# S7CAS-PLEIADES-CARTE-MERE_P20_Ethernet.net
KiCad netlist of a schematic drawn in Altium Designer
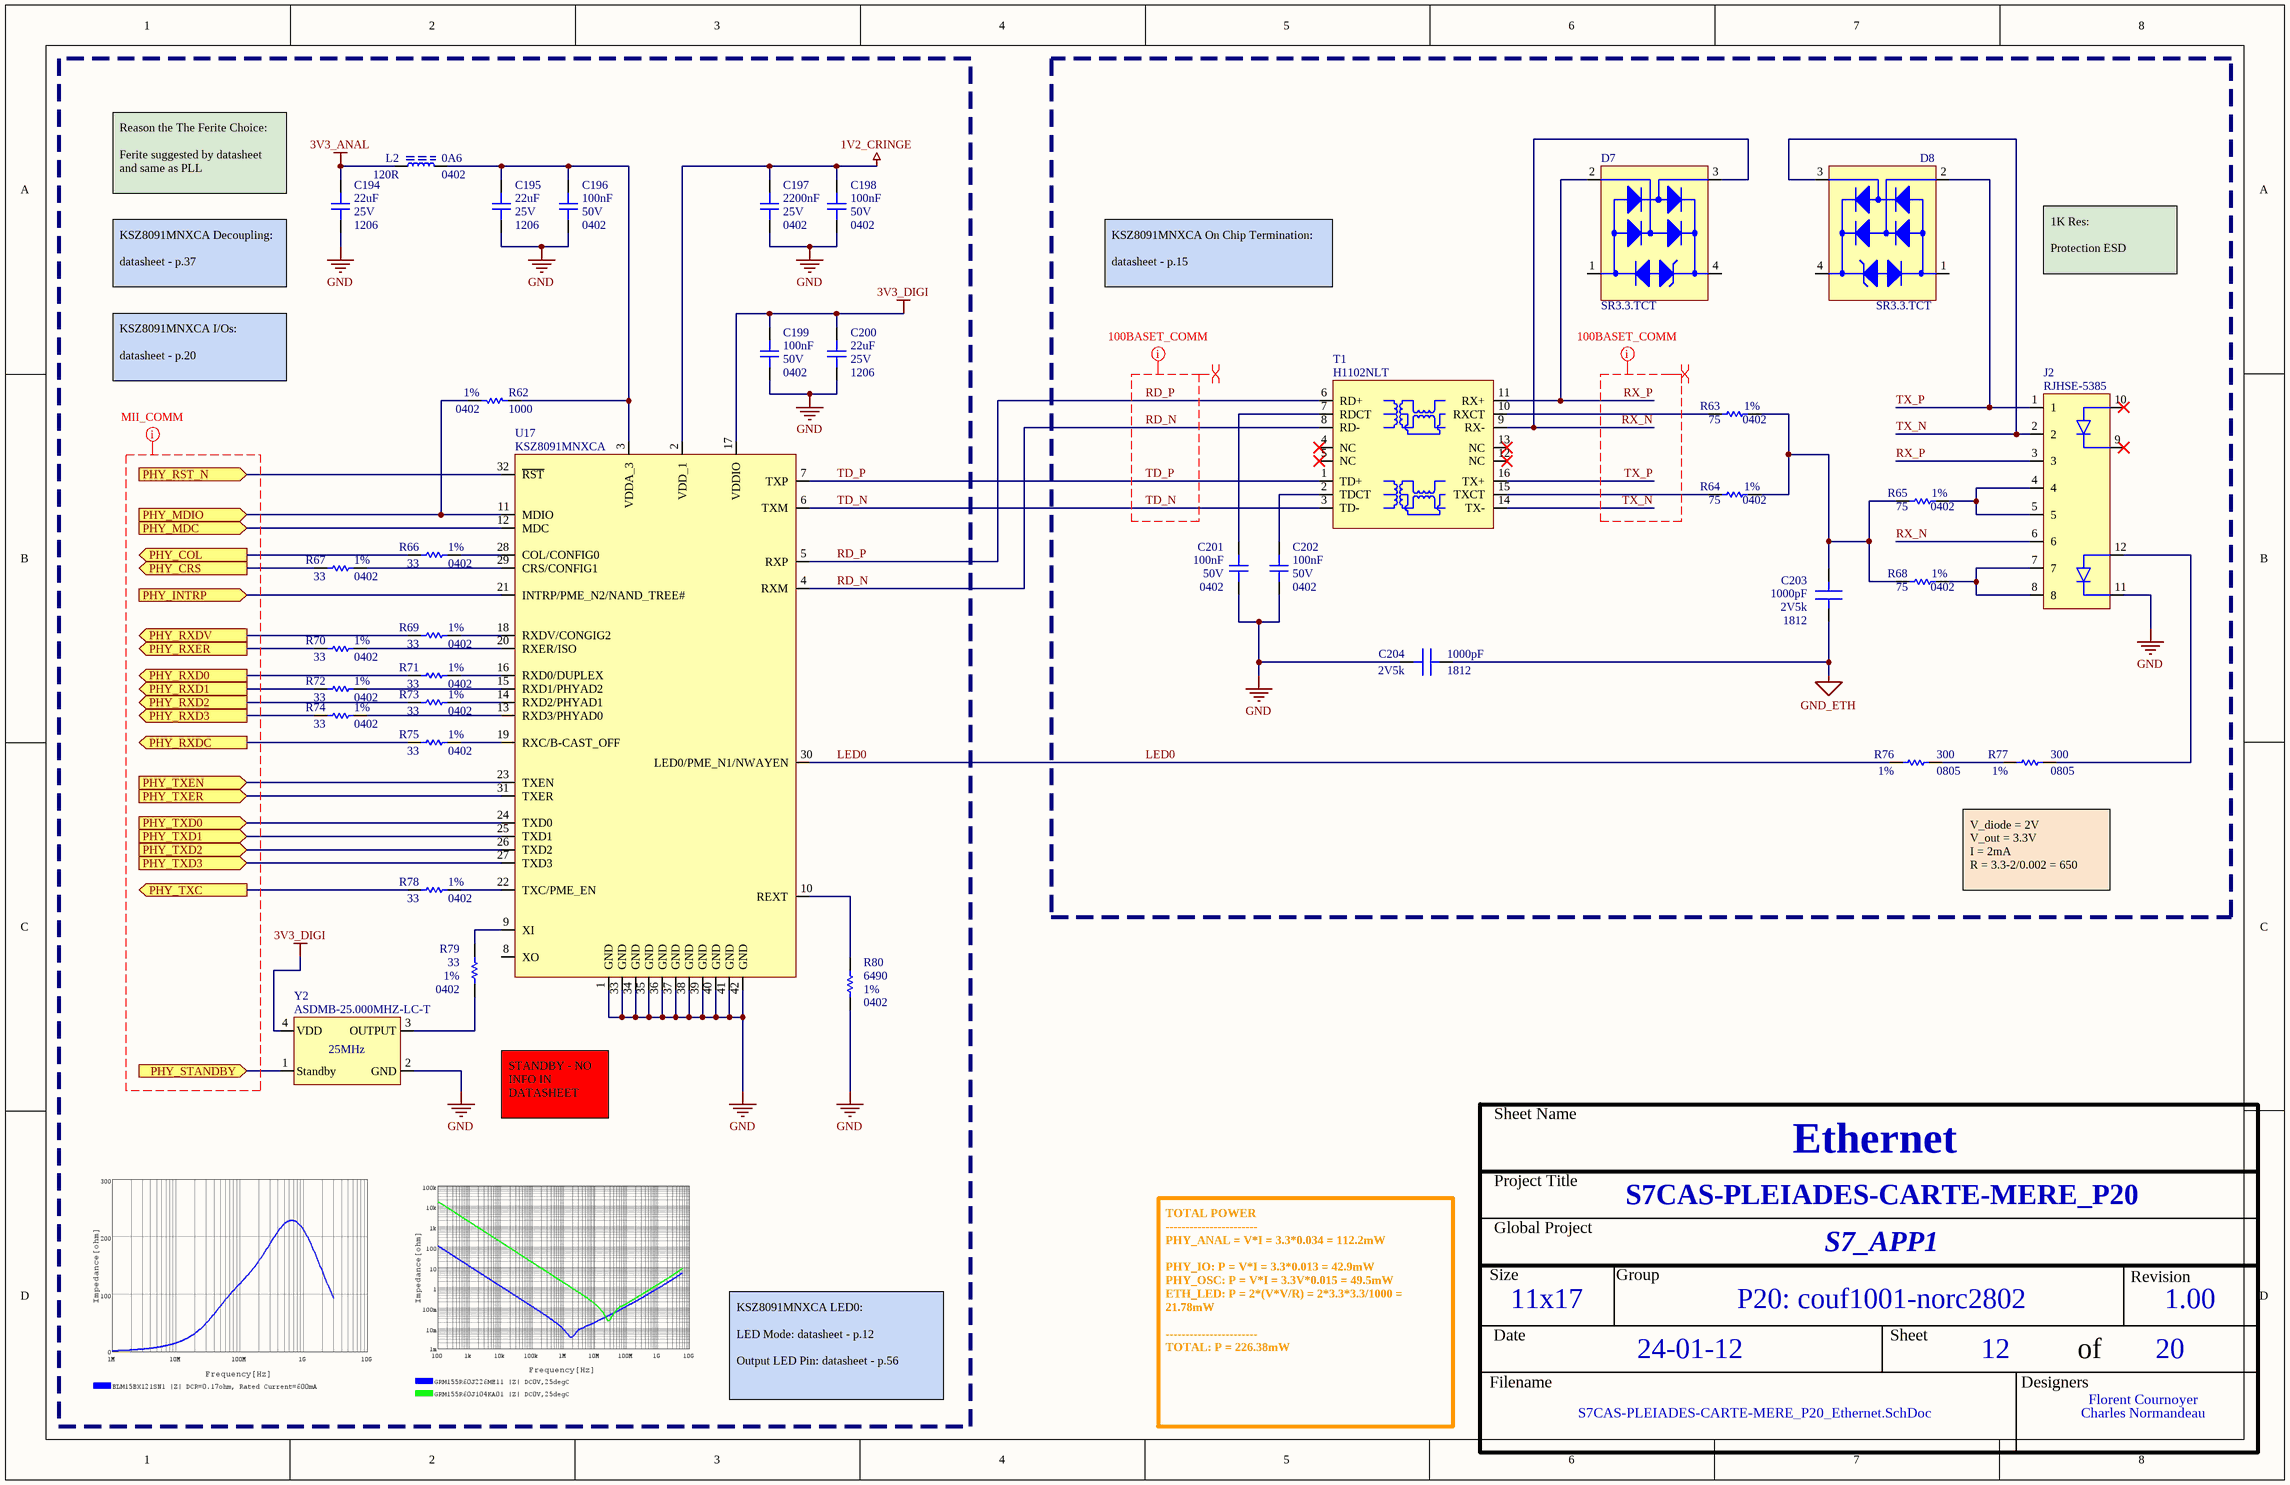
[diagram p0: S7CAS-PLEIADES-CARTE-MERE_P20_Ethernet.SchDoc]

(export (version "E")
  (design (tool "Eeschema 10.0.6"))
  (components
    (comp (ref "C194")
      (value "22uF")
      (footprint "CAP_1206")
      (description "CAP - 1206")
      (fields
        (field (name "MFG PART NUMBER") "GRM31CC81E226KE11")
        (field (name "VOLTAGE") "25V")
        (field (name "PACKAGE") "1206")
        (field (name "CREATEDBY") "Jonathan Bouchard")
      )
      (libsource (lib "S7CAS_LIB2023") (part "CAP - 1206"))
    )
    (comp (ref "C195")
      (value "22uF")
      (footprint "CAP_1206")
      (description "CAP - 1206")
      (fields
        (field (name "MFG PART NUMBER") "GRM31CC81E226KE11")
        (field (name "VOLTAGE") "25V")
        (field (name "PACKAGE") "1206")
        (field (name "CREATEDBY") "Jonathan Bouchard")
      )
      (libsource (lib "S7CAS_LIB2023") (part "CAP - 1206"))
    )
    (comp (ref "C196")
      (value "100nF")
      (footprint "CAP_0402")
      (description "CAP - 0402")
      (fields
        (field (name "MFG PART NUMBER") "GRM155R61H104KE14")
        (field (name "VOLTAGE") "50V")
        (field (name "PACKAGE") "0402")
        (field (name "CREATEDBY") "Jonathan Bouchard")
      )
      (libsource (lib "S7CAS_LIB2023") (part "CAP - 0402"))
    )
    (comp (ref "C197")
      (value "2200nF")
      (footprint "CAP_0402")
      (description "CAP - 0402")
      (fields
        (field (name "MFG PART NUMBER") "GRM155R61E225KE11")
        (field (name "VOLTAGE") "25V")
        (field (name "PACKAGE") "0402")
        (field (name "CREATEDBY") "Jonathan Bouchard")
      )
      (libsource (lib "S7CAS_LIB2023") (part "CAP - 0402"))
    )
    (comp (ref "C198")
      (value "100nF")
      (footprint "CAP_0402")
      (description "CAP - 0402")
      (fields
        (field (name "MFG PART NUMBER") "GRM155R61H104KE14")
        (field (name "VOLTAGE") "50V")
        (field (name "PACKAGE") "0402")
        (field (name "CREATEDBY") "Jonathan Bouchard")
      )
      (libsource (lib "S7CAS_LIB2023") (part "CAP - 0402"))
    )
    (comp (ref "C199")
      (value "100nF")
      (footprint "CAP_0402")
      (description "CAP - 0402")
      (fields
        (field (name "MFG PART NUMBER") "GRM155R61H104KE14")
        (field (name "VOLTAGE") "50V")
        (field (name "PACKAGE") "0402")
        (field (name "CREATEDBY") "Jonathan Bouchard")
      )
      (libsource (lib "S7CAS_LIB2023") (part "CAP - 0402"))
    )
    (comp (ref "C200")
      (value "22uF")
      (footprint "CAP_1206")
      (description "CAP - 1206")
      (fields
        (field (name "MFG PART NUMBER") "GRM31CC81E226KE11")
        (field (name "VOLTAGE") "25V")
        (field (name "PACKAGE") "1206")
        (field (name "CREATEDBY") "Jonathan Bouchard")
      )
      (libsource (lib "S7CAS_LIB2023") (part "CAP - 1206"))
    )
    (comp (ref "C201")
      (value "100nF")
      (footprint "CAP_0402")
      (description "CAP - 0402")
      (fields
        (field (name "MFG PART NUMBER") "GRM155R61H104KE14")
        (field (name "VOLTAGE") "50V")
        (field (name "PACKAGE") "0402")
        (field (name "CREATEDBY") "Jonathan Bouchard")
      )
      (libsource (lib "S7CAS_LIB2023") (part "CAP - 0402"))
    )
    (comp (ref "C202")
      (value "100nF")
      (footprint "CAP_0402")
      (description "CAP - 0402")
      (fields
        (field (name "MFG PART NUMBER") "GRM155R61H104KE14")
        (field (name "VOLTAGE") "50V")
        (field (name "PACKAGE") "0402")
        (field (name "CREATEDBY") "Jonathan Bouchard")
      )
      (libsource (lib "S7CAS_LIB2023") (part "CAP - 0402"))
    )
    (comp (ref "C203")
      (value "1000pF")
      (footprint "CAP_CER_1812")
      (description "CAP - CER 1000PF 2.5KV X7R - 1812")
      (fields
        (field (name "TOLERANCE") "10%")
        (field (name "PACKAGE") "1812")
        (field (name "VOLTAGE RATING") "2V5k")
        (field (name "Comment") "1812WC102KAT1A")
      )
      (libsource (lib "LIB_TEMP_P20_FLORENT_COURNOYER_SCH") (part "CAP_CER_1812WC102KAT1A"))
    )
    (comp (ref "C204")
      (value "1000pF")
      (footprint "CAP_CER_1812")
      (description "CAP - CER 1000PF 2.5KV X7R - 1812")
      (fields
        (field (name "TOLERANCE") "10%")
        (field (name "PACKAGE") "1812")
        (field (name "VOLTAGE RATING") "2V5k")
        (field (name "Comment") "1812WC102KAT1A")
      )
      (libsource (lib "LIB_TEMP_P20_FLORENT_COURNOYER_SCH") (part "CAP_CER_1812WC102KAT1A"))
    )
    (comp (ref "D7")
      (value "SR3.3.TCT")
      (footprint "TVS_SR3.3.TCT")
      (description "TVS - DIODE ARRAY 3.3V 150W - SOT143-4")
      (fields
        (field (name "MFG") "Semtech")
        (field (name "POWER") "150W")
        (field (name "CREATEDBY") "Jonathan Bouchard")
      )
      (libsource (lib "S7CAS_LIB2023") (part "TVS_SR3.3.TCT"))
    )
    (comp (ref "D8")
      (value "SR3.3.TCT")
      (footprint "TVS_SR3.3.TCT")
      (description "TVS - DIODE ARRAY 3.3V 150W - SOT143-4")
      (fields
        (field (name "MFG") "Semtech")
        (field (name "POWER") "150W")
        (field (name "CREATEDBY") "Jonathan Bouchard")
      )
      (libsource (lib "") (part "TVS_SR3.3.TCT_1"))
    )
    (comp (ref "J2")
      (value "RJHSE-5385")
      (footprint "CONN_ETHERNET_RJHSE-5385")
      (description "CONN - MOD JACK RJ45 R/A ETHERNET - TH")
      (fields (field (name "MFG") "Amphenol") (field (name "CREATEDBY") "Jonathan Bouchard"))
      (libsource (lib "S7CAS_LIB2023") (part "CONN_ETHERNET_RJHSE-5385"))
    )
    (comp (ref "L2")
      (value "120R")
      (footprint "FER_0402")
      (description "FER - 0402")
      (fields
        (field (name "MFG PART NUMBER") "BLM15BX121SN1")
        (field (name "CURRENT") "0A6")
        (field (name "PACKAGE") "0402")
        (field (name "CREATEDBY") "Jonathan Bouchard")
      )
      (libsource (lib "S7CAS_LIB2023") (part "FER - 0402"))
    )
    (comp (ref "R62")
      (value "1000")
      (footprint "RES_0402")
      (description "RES - 0402")
      (fields
        (field (name "VOLTAGE") "50V")
        (field (name "MFG PART NUMBER") "MCS04020C1001FE000")
        (field (name "PACKAGE") "0402")
        (field (name "PRECISION") "1%")
        (field (name "CREATEDBY") "Jonathan Bouchard")
      )
      (libsource (lib "S7CAS_LIB2023") (part "RES - 0402"))
    )
    (comp (ref "R63")
      (value "75")
      (footprint "RES_0402")
      (description "RES - 0402")
      (fields
        (field (name "VOLTAGE") "50V")
        (field (name "MFG PART NUMBER") "SG73P")
        (field (name "PACKAGE") "0402")
        (field (name "PRECISION") "1%")
        (field (name "CREATEDBY") "Jonathan Bouchard")
      )
      (libsource (lib "S7CAS_LIB2023") (part "RES - 0402"))
    )
    (comp (ref "R64")
      (value "75")
      (footprint "RES_0402")
      (description "RES - 0402")
      (fields
        (field (name "VOLTAGE") "50V")
        (field (name "MFG PART NUMBER") "SG73P")
        (field (name "PACKAGE") "0402")
        (field (name "PRECISION") "1%")
        (field (name "CREATEDBY") "Jonathan Bouchard")
      )
      (libsource (lib "S7CAS_LIB2023") (part "RES - 0402"))
    )
    (comp (ref "R65")
      (value "75")
      (footprint "RES_0402")
      (description "RES - 0402")
      (fields
        (field (name "VOLTAGE") "50V")
        (field (name "MFG PART NUMBER") "SG73P")
        (field (name "PACKAGE") "0402")
        (field (name "PRECISION") "1%")
        (field (name "CREATEDBY") "Jonathan Bouchard")
      )
      (libsource (lib "S7CAS_LIB2023") (part "RES - 0402"))
    )
    (comp (ref "R66")
      (value "33")
      (footprint "RES_0402")
      (description "RES - 0402")
      (fields
        (field (name "VOLTAGE") "50V")
        (field (name "MFG PART NUMBER") "CRCW040233R0FKEDC")
        (field (name "PACKAGE") "0402")
        (field (name "PRECISION") "1%")
        (field (name "CREATEDBY") "Jonathan Bouchard")
      )
      (libsource (lib "S7CAS_LIB2023") (part "RES - 0402"))
    )
    (comp (ref "R67")
      (value "33")
      (footprint "RES_0402")
      (description "RES - 0402")
      (fields
        (field (name "VOLTAGE") "50V")
        (field (name "MFG PART NUMBER") "CRCW040233R0FKEDC")
        (field (name "PACKAGE") "0402")
        (field (name "PRECISION") "1%")
        (field (name "CREATEDBY") "Jonathan Bouchard")
      )
      (libsource (lib "S7CAS_LIB2023") (part "RES - 0402"))
    )
    (comp (ref "R68")
      (value "75")
      (footprint "RES_0402")
      (description "RES - 0402")
      (fields
        (field (name "VOLTAGE") "50V")
        (field (name "MFG PART NUMBER") "SG73P")
        (field (name "PACKAGE") "0402")
        (field (name "PRECISION") "1%")
        (field (name "CREATEDBY") "Jonathan Bouchard")
      )
      (libsource (lib "S7CAS_LIB2023") (part "RES - 0402"))
    )
    (comp (ref "R69")
      (value "33")
      (footprint "RES_0402")
      (description "RES - 0402")
      (fields
        (field (name "VOLTAGE") "50V")
        (field (name "MFG PART NUMBER") "CRCW040233R0FKEDC")
        (field (name "PACKAGE") "0402")
        (field (name "PRECISION") "1%")
        (field (name "CREATEDBY") "Jonathan Bouchard")
      )
      (libsource (lib "S7CAS_LIB2023") (part "RES - 0402"))
    )
    (comp (ref "R70")
      (value "33")
      (footprint "RES_0402")
      (description "RES - 0402")
      (fields
        (field (name "VOLTAGE") "50V")
        (field (name "MFG PART NUMBER") "CRCW040233R0FKEDC")
        (field (name "PACKAGE") "0402")
        (field (name "PRECISION") "1%")
        (field (name "CREATEDBY") "Jonathan Bouchard")
      )
      (libsource (lib "S7CAS_LIB2023") (part "RES - 0402"))
    )
    (comp (ref "R71")
      (value "33")
      (footprint "RES_0402")
      (description "RES - 0402")
      (fields
        (field (name "VOLTAGE") "50V")
        (field (name "MFG PART NUMBER") "CRCW040233R0FKEDC")
        (field (name "PACKAGE") "0402")
        (field (name "PRECISION") "1%")
        (field (name "CREATEDBY") "Jonathan Bouchard")
      )
      (libsource (lib "S7CAS_LIB2023") (part "RES - 0402"))
    )
    (comp (ref "R72")
      (value "33")
      (footprint "RES_0402")
      (description "RES - 0402")
      (fields
        (field (name "VOLTAGE") "50V")
        (field (name "MFG PART NUMBER") "CRCW040233R0FKEDC")
        (field (name "PACKAGE") "0402")
        (field (name "PRECISION") "1%")
        (field (name "CREATEDBY") "Jonathan Bouchard")
      )
      (libsource (lib "S7CAS_LIB2023") (part "RES - 0402"))
    )
    (comp (ref "R73")
      (value "33")
      (footprint "RES_0402")
      (description "RES - 0402")
      (fields
        (field (name "VOLTAGE") "50V")
        (field (name "MFG PART NUMBER") "CRCW040233R0FKEDC")
        (field (name "PACKAGE") "0402")
        (field (name "PRECISION") "1%")
        (field (name "CREATEDBY") "Jonathan Bouchard")
      )
      (libsource (lib "S7CAS_LIB2023") (part "RES - 0402"))
    )
    (comp (ref "R74")
      (value "33")
      (footprint "RES_0402")
      (description "RES - 0402")
      (fields
        (field (name "VOLTAGE") "50V")
        (field (name "MFG PART NUMBER") "CRCW040233R0FKEDC")
        (field (name "PACKAGE") "0402")
        (field (name "PRECISION") "1%")
        (field (name "CREATEDBY") "Jonathan Bouchard")
      )
      (libsource (lib "S7CAS_LIB2023") (part "RES - 0402"))
    )
    (comp (ref "R75")
      (value "33")
      (footprint "RES_0402")
      (description "RES - 0402")
      (fields
        (field (name "VOLTAGE") "50V")
        (field (name "MFG PART NUMBER") "CRCW040233R0FKEDC")
        (field (name "PACKAGE") "0402")
        (field (name "PRECISION") "1%")
        (field (name "CREATEDBY") "Jonathan Bouchard")
      )
      (libsource (lib "S7CAS_LIB2023") (part "RES - 0402"))
    )
    (comp (ref "R76")
      (value "300")
      (footprint "RES_0805")
      (description "RES - 0805")
      (fields
        (field (name "MFG PART NUMBER") "CRM0805-FX-1000ELF")
        (field (name "PACKAGE") "0805")
        (field (name "PRECISION") "1%")
        (field (name "CREATEDBY") "Jonathan Bouchard")
      )
      (libsource (lib "S7CAS_LIB2023") (part "RES - 0805"))
    )
    (comp (ref "R77")
      (value "300")
      (footprint "RES_0805")
      (description "RES - 0805")
      (fields
        (field (name "MFG PART NUMBER") "CRM0805-FX-1000ELF")
        (field (name "PACKAGE") "0805")
        (field (name "PRECISION") "1%")
        (field (name "CREATEDBY") "Jonathan Bouchard")
      )
      (libsource (lib "S7CAS_LIB2023") (part "RES - 0805"))
    )
    (comp (ref "R78")
      (value "33")
      (footprint "RES_0402")
      (description "RES - 0402")
      (fields
        (field (name "VOLTAGE") "50V")
        (field (name "MFG PART NUMBER") "CRCW040233R0FKEDC")
        (field (name "PACKAGE") "0402")
        (field (name "PRECISION") "1%")
        (field (name "CREATEDBY") "Jonathan Bouchard")
      )
      (libsource (lib "S7CAS_LIB2023") (part "RES - 0402"))
    )
    (comp (ref "R79")
      (value "33")
      (footprint "RES_0402")
      (description "RES - 0402")
      (fields
        (field (name "VOLTAGE") "50V")
        (field (name "MFG PART NUMBER") "CRCW040233R0FKEDC")
        (field (name "PACKAGE") "0402")
        (field (name "PRECISION") "1%")
        (field (name "CREATEDBY") "Jonathan Bouchard")
      )
      (libsource (lib "S7CAS_LIB2023") (part "RES - 0402"))
    )
    (comp (ref "R80")
      (value "6490")
      (footprint "RES_0402")
      (description "RES - 0402")
      (fields
        (field (name "VOLTAGE") "50V")
        (field (name "MFG PART NUMBER") "CRCW04026K49FKEDC")
        (field (name "PACKAGE") "0402")
        (field (name "PRECISION") "1%")
        (field (name "CREATEDBY") "Jonathan Bouchard")
      )
      (libsource (lib "S7CAS_LIB2023") (part "RES - 0402"))
    )
    (comp (ref "T1")
      (value "H1102NLT")
      (footprint "TRANSFO_H1102NLT")
      (description "TRANSFO - ETHERNET 10/100B-TX - SMD-16")
      (fields (field (name "MFG") "Pulse Eng.") (field (name "CREATEDBY") "Jonathan Bouchard"))
      (libsource (lib "S7CAS_LIB2023") (part "TRANSFO_H1102NLT"))
    )
    (comp (ref "U17")
      (value "KSZ8091MNXCA")
      (footprint "COM_ETH_PHY_KSZ8091MNXCA")
      (description "COM - ETHERNET PHY 10/100 - QFN-32")
      (fields
        (field (name "VOLTAGE") "1.8V, 2.5V, 3.3V")
        (field (name "MFG") "Micrel")
        (field (name "CREATEDBY") "Jonathan Bouchard")
      )
      (libsource (lib "S7CAS_LIB2023") (part "COM_ETH_PHY_KSZ8091MNXCA"))
    )
    (comp (ref "Y2")
      (value "ASDMB-25.000MHZ-LC-T")
      (footprint "OSC_ASDMB-25.000MHZ-LC-T")
      (description "OSC - 25MHz XO (Standard) LVCMOS - 4-SMD, No Lead")
      (fields
        (field (name "TOLERANCE") "±50ppm")
        (field (name "CREATEDBY/DATE") "Joël Lemay 2019-03-29")
        (field (name "VERIFIEDBY") "C. Paulin - 29 mai 2019")
      )
      (libsource (lib "S7CAS_LIB2023") (part "OSC_ASDMB-25.000MHZ-LC-T"))
    )
  )
  (nets
    (net (code "1") (name "/LED0") (class "Default")
      (node (ref "R76") (pin "2") (pinfunction "2_2") (pintype "passive"))
      (node (ref "U17") (pin "30") (pinfunction "LED0/PME_N1/NWAYEN_30") (pintype "passive"))
    )
    (net (code "2") (name "/PHY_COL") (class "Default")
      (node (ref "R66") (pin "2") (pinfunction "2_2") (pintype "passive"))
    )
    (net (code "3") (name "/PHY_CRS") (class "Default")
      (node (ref "R67") (pin "2") (pinfunction "2_2") (pintype "passive"))
    )
    (net (code "4") (name "/PHY_INTRP") (class "Default")
      (node (ref "U17") (pin "21") (pinfunction "INTRP/PME_N2/NAND_TREE#_21") (pintype "passive"))
    )
    (net (code "5") (name "/PHY_MDC") (class "Default")
      (node (ref "U17") (pin "12") (pinfunction "MDC_12") (pintype "passive"))
    )
    (net (code "6") (name "/PHY_MDIO") (class "Default")
      (node (ref "R62") (pin "1") (pinfunction "1_1") (pintype "passive"))
      (node (ref "U17") (pin "11") (pinfunction "MDIO_11") (pintype "passive"))
    )
    (net (code "7") (name "/PHY_RST_N") (class "Default")
      (node (ref "U17") (pin "32") (pinfunction "RST_32") (pintype "passive"))
    )
    (net (code "8") (name "/PHY_RXD0") (class "Default")
      (node (ref "R71") (pin "2") (pinfunction "2_2") (pintype "passive"))
    )
    (net (code "9") (name "/PHY_RXD1") (class "Default")
      (node (ref "R72") (pin "2") (pinfunction "2_2") (pintype "passive"))
    )
    (net (code "10") (name "/PHY_RXD2") (class "Default")
      (node (ref "R73") (pin "2") (pinfunction "2_2") (pintype "passive"))
    )
    (net (code "11") (name "/PHY_RXD3") (class "Default")
      (node (ref "R74") (pin "2") (pinfunction "2_2") (pintype "passive"))
    )
    (net (code "12") (name "/PHY_RXDC") (class "Default")
      (node (ref "R75") (pin "2") (pinfunction "2_2") (pintype "passive"))
    )
    (net (code "13") (name "/PHY_RXDV") (class "Default")
      (node (ref "R69") (pin "2") (pinfunction "2_2") (pintype "passive"))
    )
    (net (code "14") (name "/PHY_RXER") (class "Default")
      (node (ref "R70") (pin "2") (pinfunction "2_2") (pintype "passive"))
    )
    (net (code "15") (name "/PHY_STANDBY") (class "Default")
      (node (ref "Y2") (pin "1") (pinfunction "Standby_1") (pintype "passive"))
    )
    (net (code "16") (name "/PHY_TXC") (class "Default")
      (node (ref "R78") (pin "2") (pinfunction "2_2") (pintype "passive"))
    )
    (net (code "17") (name "/PHY_TXD0") (class "Default")
      (node (ref "U17") (pin "24") (pinfunction "TXD0_24") (pintype "passive"))
    )
    (net (code "18") (name "/PHY_TXD1") (class "Default")
      (node (ref "U17") (pin "25") (pinfunction "TXD1_25") (pintype "passive"))
    )
    (net (code "19") (name "/PHY_TXD2") (class "Default")
      (node (ref "U17") (pin "26") (pinfunction "TXD2_26") (pintype "passive"))
    )
    (net (code "20") (name "/PHY_TXD3") (class "Default")
      (node (ref "U17") (pin "27") (pinfunction "TXD3_27") (pintype "passive"))
    )
    (net (code "21") (name "/PHY_TXEN") (class "Default")
      (node (ref "U17") (pin "23") (pinfunction "TXEN_23") (pintype "passive"))
    )
    (net (code "22") (name "/PHY_TXER") (class "Default")
      (node (ref "U17") (pin "31") (pinfunction "TXER_31") (pintype "passive"))
    )
    (net (code "23") (name "/RD_N") (class "Default")
      (node (ref "T1") (pin "8") (pinfunction "RD-_8") (pintype "passive"))
      (node (ref "U17") (pin "4") (pinfunction "RXM_4") (pintype "passive"))
    )
    (net (code "24") (name "/RD_P") (class "Default")
      (node (ref "T1") (pin "6") (pinfunction "RD+_6") (pintype "passive"))
      (node (ref "U17") (pin "5") (pinfunction "RXP_5") (pintype "passive"))
    )
    (net (code "25") (name "/RX_N") (class "Default")
      (node (ref "D7") (pin "3") (pintype "passive"))
      (node (ref "J2") (pin "6") (pinfunction "6_6") (pintype "passive"))
      (node (ref "T1") (pin "9") (pinfunction "RX-_9") (pintype "passive"))
    )
    (net (code "26") (name "/RX_P") (class "Default")
      (node (ref "D7") (pin "2") (pinfunction "VN_2") (pintype "passive"))
      (node (ref "J2") (pin "3") (pinfunction "3_3") (pintype "passive"))
      (node (ref "T1") (pin "11") (pinfunction "RX+_11") (pintype "passive"))
    )
    (net (code "27") (name "/TD_N") (class "Default")
      (node (ref "T1") (pin "3") (pinfunction "TD-_3") (pintype "passive"))
      (node (ref "U17") (pin "6") (pinfunction "TXM_6") (pintype "passive"))
    )
    (net (code "28") (name "/TD_P") (class "Default")
      (node (ref "T1") (pin "1") (pinfunction "TD+_1") (pintype "passive"))
      (node (ref "U17") (pin "7") (pinfunction "TXP_7") (pintype "passive"))
    )
    (net (code "29") (name "/TX_N") (class "Default")
      (node (ref "D8") (pin "3") (pintype "passive"))
      (node (ref "J2") (pin "2") (pinfunction "2_2") (pintype "passive"))
      (node (ref "T1") (pin "14") (pinfunction "TX-_14") (pintype "passive"))
    )
    (net (code "30") (name "/TX_P") (class "Default")
      (node (ref "D8") (pin "2") (pinfunction "VN_2") (pintype "passive"))
      (node (ref "J2") (pin "1") (pinfunction "1_1") (pintype "passive"))
      (node (ref "T1") (pin "16") (pinfunction "TX+_16") (pintype "passive"))
    )
    (net (code "31") (name "1V2_CRINGE") (class "Default")
      (node (ref "C197") (pin "2") (pinfunction "2_2") (pintype "passive"))
      (node (ref "C198") (pin "2") (pinfunction "2_2") (pintype "passive"))
      (node (ref "U17") (pin "2") (pinfunction "VDD_1_2") (pintype "power_in"))
    )
    (net (code "32") (name "3V3_ANAL") (class "Default")
      (node (ref "C194") (pin "2") (pinfunction "2_2") (pintype "passive"))
      (node (ref "L2") (pin "2") (pinfunction "2_2") (pintype "passive"))
    )
    (net (code "33") (name "3V3_DIGI") (class "Default")
      (node (ref "C199") (pin "2") (pinfunction "2_2") (pintype "passive"))
      (node (ref "C200") (pin "2") (pinfunction "2_2") (pintype "passive"))
      (node (ref "U17") (pin "17") (pinfunction "VDDIO_17") (pintype "power_in"))
      (node (ref "Y2") (pin "4") (pinfunction "VDD_4") (pintype "passive"))
    )
    (net (code "34") (name "GND") (class "Default")
      (node (ref "C194") (pin "1") (pinfunction "1_1") (pintype "passive"))
      (node (ref "C195") (pin "1") (pinfunction "1_1") (pintype "passive"))
      (node (ref "C196") (pin "1") (pinfunction "1_1") (pintype "passive"))
      (node (ref "C197") (pin "1") (pinfunction "1_1") (pintype "passive"))
      (node (ref "C198") (pin "1") (pinfunction "1_1") (pintype "passive"))
      (node (ref "C199") (pin "1") (pinfunction "1_1") (pintype "passive"))
      (node (ref "C200") (pin "1") (pinfunction "1_1") (pintype "passive"))
      (node (ref "C201") (pin "1") (pinfunction "1_1") (pintype "passive"))
      (node (ref "C202") (pin "1") (pinfunction "1_1") (pintype "passive"))
      (node (ref "C204") (pin "2") (pinfunction "2_2") (pintype "passive"))
      (node (ref "J2") (pin "11") (pinfunction "LED2_K_11") (pintype "passive"))
      (node (ref "R80") (pin "1") (pinfunction "1_1") (pintype "passive"))
      (node (ref "U17") (pin "1") (pinfunction "GND_1") (pintype "passive"))
      (node (ref "U17") (pin "33") (pinfunction "GND_33") (pintype "passive"))
      (node (ref "U17") (pin "34") (pinfunction "GND_34") (pintype "passive"))
      (node (ref "U17") (pin "35") (pinfunction "GND_35") (pintype "passive"))
      (node (ref "U17") (pin "36") (pinfunction "GND_36") (pintype "passive"))
      (node (ref "U17") (pin "37") (pinfunction "GND_37") (pintype "passive"))
      (node (ref "U17") (pin "38") (pinfunction "GND_38") (pintype "passive"))
      (node (ref "U17") (pin "39") (pinfunction "GND_39") (pintype "passive"))
      (node (ref "U17") (pin "40") (pinfunction "GND_40") (pintype "passive"))
      (node (ref "U17") (pin "41") (pinfunction "GND_41") (pintype "passive"))
      (node (ref "U17") (pin "42") (pinfunction "GND_42") (pintype "passive"))
      (node (ref "Y2") (pin "2") (pinfunction "GND_2") (pintype "passive"))
    )
    (net (code "35") (name "GND_ETH") (class "Default")
      (node (ref "C203") (pin "2") (pinfunction "2_2") (pintype "passive"))
      (node (ref "C204") (pin "1") (pinfunction "1_1") (pintype "passive"))
    )
    (net (code "36") (name "Net-(C203-Pad1)") (class "Default")
      (node (ref "C203") (pin "1") (pinfunction "1_1") (pintype "passive"))
      (node (ref "R63") (pin "1") (pinfunction "1_1") (pintype "passive"))
      (node (ref "R64") (pin "1") (pinfunction "1_1") (pintype "passive"))
      (node (ref "R65") (pin "2") (pinfunction "2_2") (pintype "passive"))
      (node (ref "R68") (pin "2") (pinfunction "2_2") (pintype "passive"))
    )
    (net (code "37") (name "Net-(J2-LED2_A)") (class "Default")
      (node (ref "J2") (pin "12") (pinfunction "LED2_A_12") (pintype "passive"))
      (node (ref "R77") (pin "1") (pinfunction "1_1") (pintype "passive"))
    )
    (net (code "38") (name "Net-(J2-Pad4)") (class "Default")
      (node (ref "J2") (pin "4") (pinfunction "4_4") (pintype "passive"))
      (node (ref "J2") (pin "5") (pinfunction "5_5") (pintype "passive"))
      (node (ref "R65") (pin "1") (pinfunction "1_1") (pintype "passive"))
    )
    (net (code "39") (name "Net-(J2-Pad7)") (class "Default")
      (node (ref "J2") (pin "7") (pinfunction "7_7") (pintype "passive"))
      (node (ref "J2") (pin "8") (pinfunction "8_8") (pintype "passive"))
      (node (ref "R68") (pin "1") (pinfunction "1_1") (pintype "passive"))
    )
    (net (code "40") (name "Net-(R76-Pad1)") (class "Default")
      (node (ref "R76") (pin "1") (pinfunction "1_1") (pintype "passive"))
      (node (ref "R77") (pin "2") (pinfunction "2_2") (pintype "passive"))
    )
    (net (code "41") (name "Net-(T1-RDCT)") (class "Default")
      (node (ref "C201") (pin "2") (pinfunction "2_2") (pintype "passive"))
      (node (ref "T1") (pin "7") (pinfunction "RDCT_7") (pintype "passive"))
    )
    (net (code "42") (name "Net-(T1-RXCT)") (class "Default")
      (node (ref "R63") (pin "2") (pinfunction "2_2") (pintype "passive"))
      (node (ref "T1") (pin "10") (pinfunction "RXCT_10") (pintype "passive"))
    )
    (net (code "43") (name "Net-(T1-TDCT)") (class "Default")
      (node (ref "C202") (pin "2") (pinfunction "2_2") (pintype "passive"))
      (node (ref "T1") (pin "2") (pinfunction "TDCT_2") (pintype "passive"))
    )
    (net (code "44") (name "Net-(T1-TXCT)") (class "Default")
      (node (ref "R64") (pin "2") (pinfunction "2_2") (pintype "passive"))
      (node (ref "T1") (pin "15") (pinfunction "TXCT_15") (pintype "passive"))
    )
    (net (code "45") (name "Net-(U17-COL{slash}CONFIG0)") (class "Default")
      (node (ref "R66") (pin "1") (pinfunction "1_1") (pintype "passive"))
      (node (ref "U17") (pin "28") (pinfunction "COL/CONFIG0_28") (pintype "passive"))
    )
    (net (code "46") (name "Net-(U17-CRS{slash}CONFIG1)") (class "Default")
      (node (ref "R67") (pin "1") (pinfunction "1_1") (pintype "passive"))
      (node (ref "U17") (pin "29") (pinfunction "CRS/CONFIG1_29") (pintype "passive"))
    )
    (net (code "47") (name "Net-(U17-REXT)") (class "Default")
      (node (ref "R80") (pin "2") (pinfunction "2_2") (pintype "passive"))
      (node (ref "U17") (pin "10") (pinfunction "REXT_10") (pintype "passive"))
    )
    (net (code "48") (name "Net-(U17-RXC{slash}B-CAST_OFF)") (class "Default")
      (node (ref "R75") (pin "1") (pinfunction "1_1") (pintype "passive"))
      (node (ref "U17") (pin "19") (pinfunction "RXC/B-CAST_OFF_19") (pintype "passive"))
    )
    (net (code "49") (name "Net-(U17-RXD0{slash}DUPLEX)") (class "Default")
      (node (ref "R71") (pin "1") (pinfunction "1_1") (pintype "passive"))
      (node (ref "U17") (pin "16") (pinfunction "RXD0/DUPLEX_16") (pintype "passive"))
    )
    (net (code "50") (name "Net-(U17-RXD1{slash}PHYAD2)") (class "Default")
      (node (ref "R72") (pin "1") (pinfunction "1_1") (pintype "passive"))
      (node (ref "U17") (pin "15") (pinfunction "RXD1/PHYAD2_15") (pintype "passive"))
    )
    (net (code "51") (name "Net-(U17-RXD2{slash}PHYAD1)") (class "Default")
      (node (ref "R73") (pin "1") (pinfunction "1_1") (pintype "passive"))
      (node (ref "U17") (pin "14") (pinfunction "RXD2/PHYAD1_14") (pintype "passive"))
    )
    (net (code "52") (name "Net-(U17-RXD3{slash}PHYAD0)") (class "Default")
      (node (ref "R74") (pin "1") (pinfunction "1_1") (pintype "passive"))
      (node (ref "U17") (pin "13") (pinfunction "RXD3/PHYAD0_13") (pintype "passive"))
    )
    (net (code "53") (name "Net-(U17-RXDV{slash}CONGIG2)") (class "Default")
      (node (ref "R69") (pin "1") (pinfunction "1_1") (pintype "passive"))
      (node (ref "U17") (pin "18") (pinfunction "RXDV/CONGIG2_18") (pintype "passive"))
    )
    (net (code "54") (name "Net-(U17-RXER{slash}ISO)") (class "Default")
      (node (ref "R70") (pin "1") (pinfunction "1_1") (pintype "passive"))
      (node (ref "U17") (pin "20") (pinfunction "RXER/ISO_20") (pintype "passive"))
    )
    (net (code "55") (name "Net-(U17-TXC{slash}PME_EN)") (class "Default")
      (node (ref "R78") (pin "1") (pinfunction "1_1") (pintype "passive"))
      (node (ref "U17") (pin "22") (pinfunction "TXC/PME_EN_22") (pintype "passive"))
    )
    (net (code "56") (name "Net-(U17-VDDA_3)") (class "Default")
      (node (ref "C195") (pin "2") (pinfunction "2_2") (pintype "passive"))
      (node (ref "C196") (pin "2") (pinfunction "2_2") (pintype "passive"))
      (node (ref "L2") (pin "1") (pinfunction "1_1") (pintype "passive"))
      (node (ref "R62") (pin "2") (pinfunction "2_2") (pintype "passive"))
      (node (ref "U17") (pin "3") (pinfunction "VDDA_3_3") (pintype "power_in"))
    )
    (net (code "57") (name "Net-(U17-XI)") (class "Default")
      (node (ref "R79") (pin "1") (pinfunction "1_1") (pintype "passive"))
      (node (ref "U17") (pin "9") (pinfunction "XI_9") (pintype "passive"))
    )
    (net (code "58") (name "Net-(Y2-OUTPUT)") (class "Default")
      (node (ref "R79") (pin "2") (pinfunction "2_2") (pintype "passive"))
      (node (ref "Y2") (pin "3") (pinfunction "OUTPUT_3") (pintype "passive"))
    )
    (net (code "59") (name "unconnected-(D7-I{slash}O-Pad1)") (class "Default")
      (node (ref "D7") (pin "1") (pinfunction "I/O_1") (pintype "passive"))
    )
    (net (code "60") (name "unconnected-(D7-Pad4)") (class "Default")
      (node (ref "D7") (pin "4") (pintype "passive"))
    )
    (net (code "61") (name "unconnected-(D8-I{slash}O-Pad1)") (class "Default")
      (node (ref "D8") (pin "1") (pinfunction "I/O_1") (pintype "passive"))
    )
    (net (code "62") (name "unconnected-(D8-Pad4)") (class "Default")
      (node (ref "D8") (pin "4") (pintype "passive"))
    )
    (net (code "63") (name "unconnected-(J2-LED1_A-Pad10)") (class "Default")
      (node (ref "J2") (pin "10") (pinfunction "LED1_A_10") (pintype "passive+no_connect"))
    )
    (net (code "64") (name "unconnected-(J2-LED1_K-Pad9)") (class "Default")
      (node (ref "J2") (pin "9") (pinfunction "LED1_K_9") (pintype "passive+no_connect"))
    )
    (net (code "65") (name "unconnected-(T1-NC-Pad4)") (class "Default")
      (node (ref "T1") (pin "4") (pinfunction "NC_4") (pintype "passive+no_connect"))
    )
    (net (code "66") (name "unconnected-(T1-NC-Pad5)") (class "Default")
      (node (ref "T1") (pin "5") (pinfunction "NC_5") (pintype "passive+no_connect"))
    )
    (net (code "67") (name "unconnected-(T1-NC-Pad12)") (class "Default")
      (node (ref "T1") (pin "12") (pinfunction "NC_12") (pintype "passive+no_connect"))
    )
    (net (code "68") (name "unconnected-(T1-NC-Pad13)") (class "Default")
      (node (ref "T1") (pin "13") (pinfunction "NC_13") (pintype "passive+no_connect"))
    )
    (net (code "69") (name "unconnected-(U17-XO-Pad8)") (class "Default")
      (node (ref "U17") (pin "8") (pinfunction "XO_8") (pintype "passive"))
    )
  )
)
